# Wacky_Racer_Schematic.net
KiCad netlist of a schematic drawn in Altium Designer
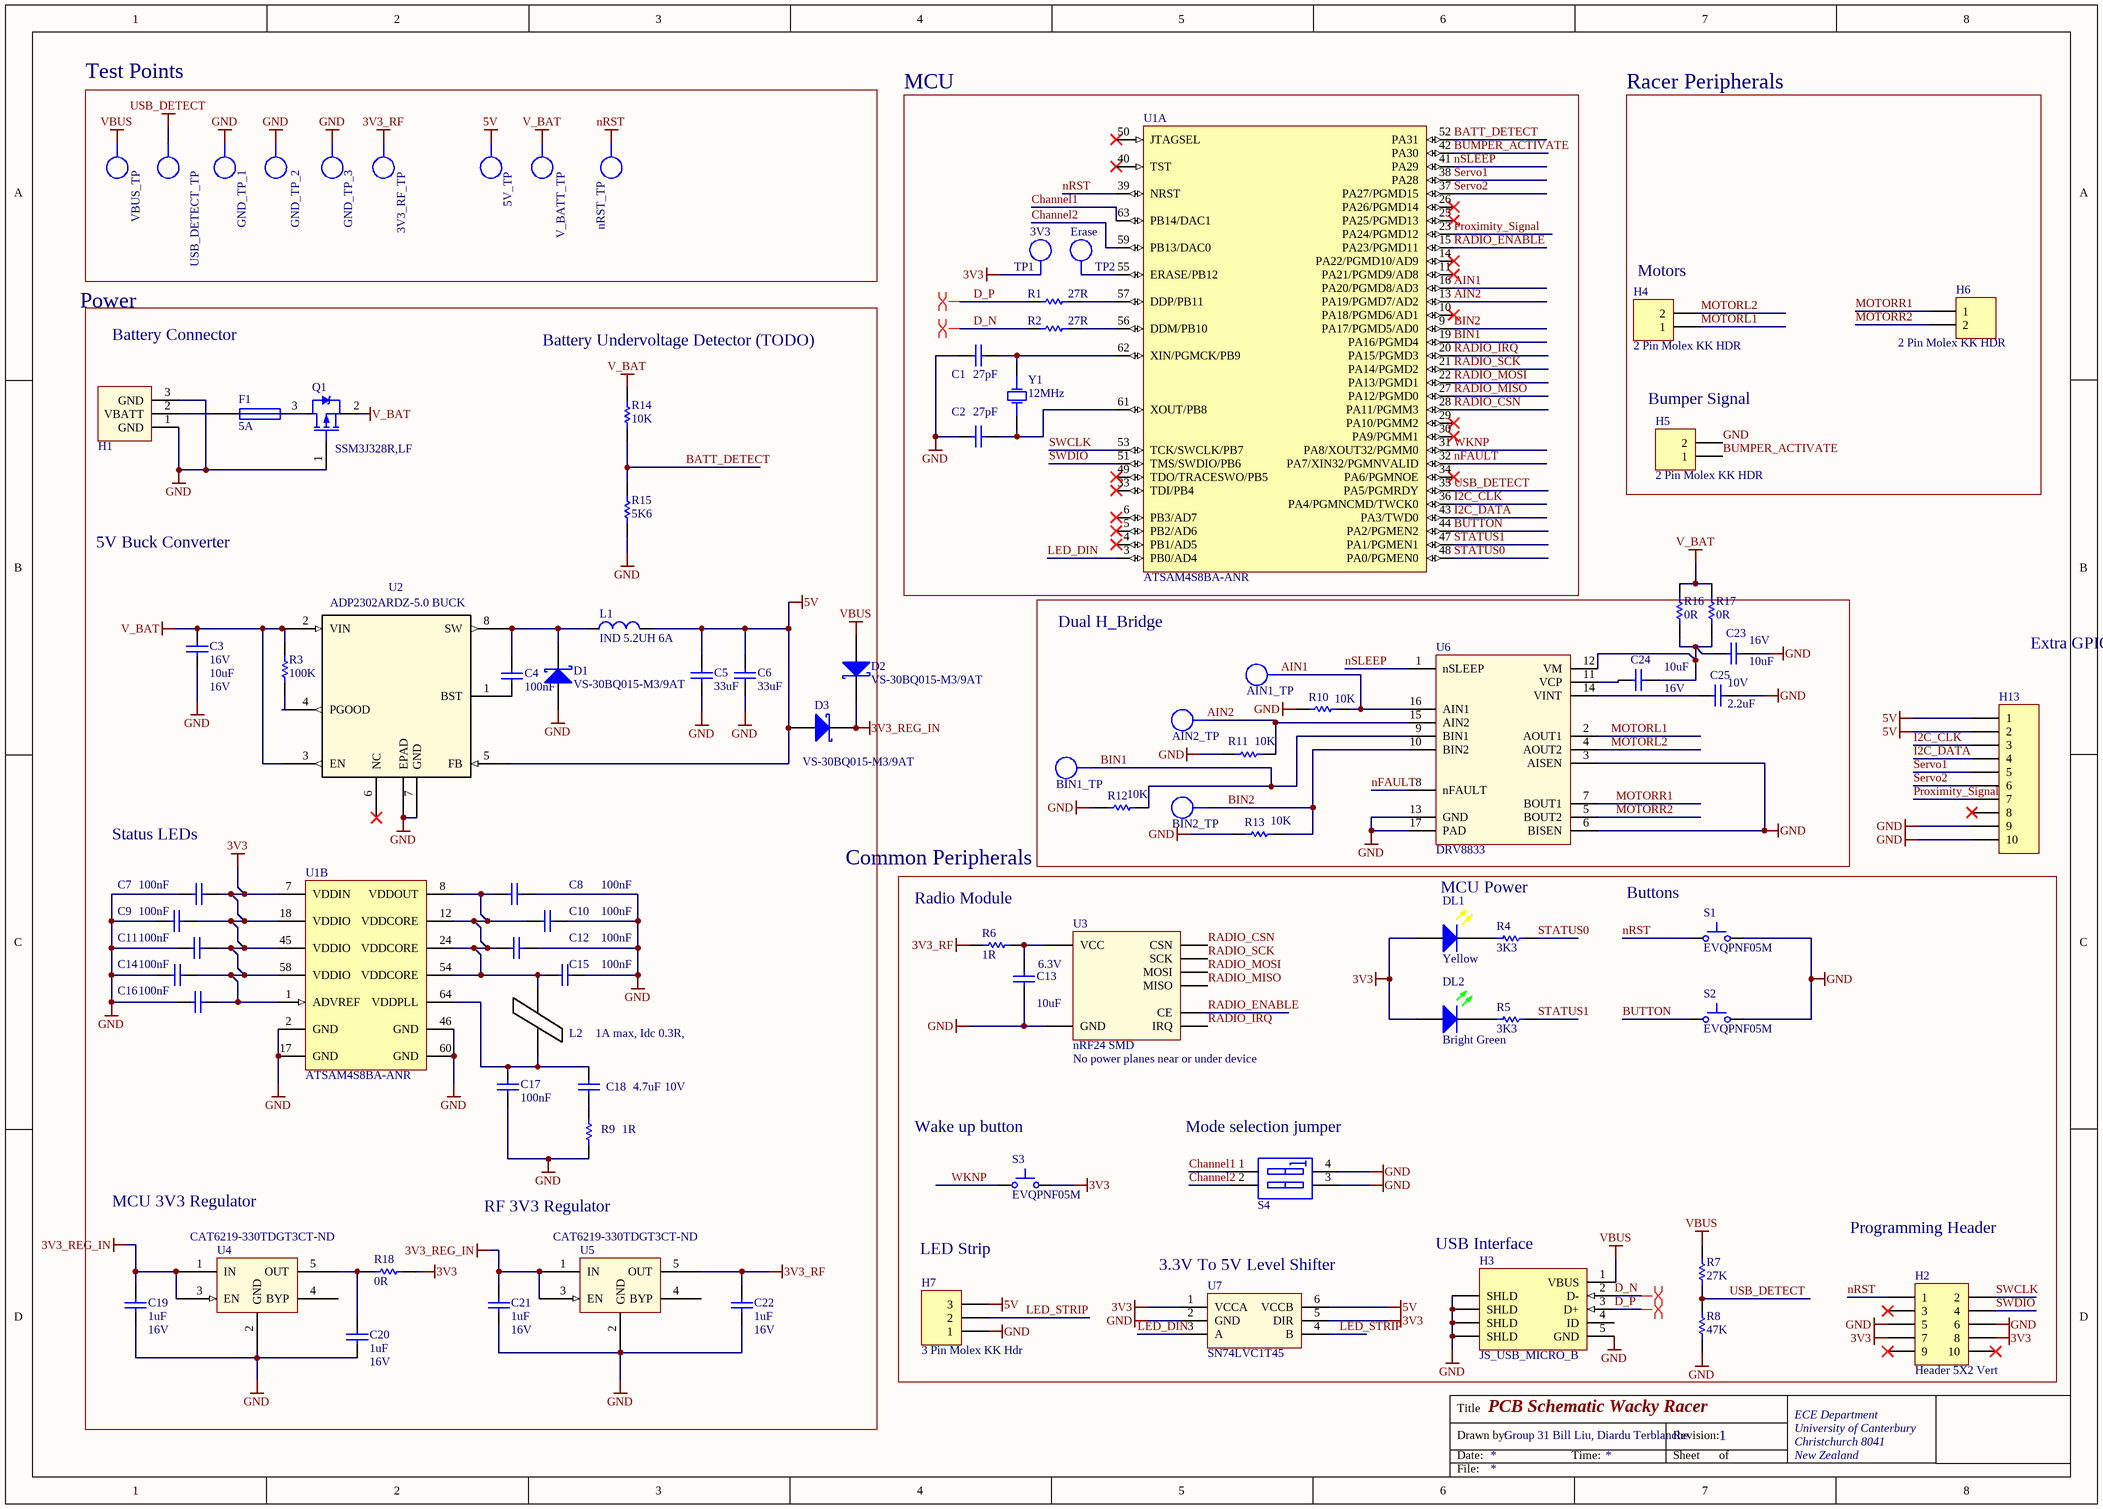
[diagram p0: Wacky Racer Schematic.schdoc]

(export (version "E")
  (design (tool "Eeschema 10.0.6"))
  (components
    (comp (ref "3V3_RF_TP")
      (value "TP")
      (footprint "TP_1206")
      (description "Test-Point 3.3x1.6x2.1mm SMD")
      (fields
        (field (name "MANUFACTURER") "Harwin Inc")
        (field (name "MANUFACTURER PART NUMBER") "S1751-46R")
      )
      (libsource (lib "ECE AD19Components_19V1") (part "TP_1206"))
    )
    (comp (ref "5V_TP")
      (value "TP")
      (footprint "TP_1206")
      (description "Test-Point 3.3x1.6x2.1mm SMD")
      (fields
        (field (name "MANUFACTURER") "Harwin Inc")
        (field (name "MANUFACTURER PART NUMBER") "S1751-46R")
      )
      (libsource (lib "ECE AD19Components_19V1") (part "TP_1206"))
    )
    (comp (ref "AIN1_TP")
      (value "TP")
      (footprint "TP_1206")
      (description "Test-Point 3.3x1.6x2.1mm SMD")
      (fields
        (field (name "MANUFACTURER") "Harwin Inc")
        (field (name "MANUFACTURER PART NUMBER") "S1751-46R")
      )
      (libsource (lib "ECE AD19Components_19V1") (part "TP_1206"))
    )
    (comp (ref "AIN2_TP")
      (value "TP")
      (footprint "TP_1206")
      (description "Test-Point 3.3x1.6x2.1mm SMD")
      (fields
        (field (name "MANUFACTURER") "Harwin Inc")
        (field (name "MANUFACTURER PART NUMBER") "S1751-46R")
      )
      (libsource (lib "ECE AD19Components_19V1") (part "TP_1206"))
    )
    (comp (ref "BIN1_TP")
      (value "TP")
      (footprint "TP_1206")
      (description "Test-Point 3.3x1.6x2.1mm SMD")
      (fields
        (field (name "MANUFACTURER") "Harwin Inc")
        (field (name "MANUFACTURER PART NUMBER") "S1751-46R")
      )
      (libsource (lib "ECE AD19Components_19V1") (part "TP_1206"))
    )
    (comp (ref "BIN2_TP")
      (value "TP")
      (footprint "TP_1206")
      (description "Test-Point 3.3x1.6x2.1mm SMD")
      (fields
        (field (name "MANUFACTURER") "Harwin Inc")
        (field (name "MANUFACTURER PART NUMBER") "S1751-46R")
      )
      (libsource (lib "ECE AD19Components_19V1") (part "TP_1206"))
    )
    (comp (ref "C1")
      (value "27pF")
      (footprint "CAPC1608L")
      (description "CAP CER 27pF NPO/COG +-5% 50V 0603")
      (libsource (lib "ECE AD19Components_19V1") (part "CC_27pF_0603"))
    )
    (comp (ref "C2")
      (value "27pF")
      (footprint "CAPC1608L")
      (description "CAP CER 27pF NPO/COG +-5% 50V 0603")
      (libsource (lib "ECE AD19Components_19V1") (part "CC_27pF_0603"))
    )
    (comp (ref "C3")
      (value "10uF")
      (footprint "CAPC2012L")
      (description "CAP CER 10uF X5R 16V 0805")
      (fields
        (field (name "MANUFACTURER") "Samsung Electro-Mechanics")
        (field (name "MANUFACTURER PART NUMBER") "CL21A106KOQNNWE")
        (field (name "VOLTAGE - RATED") "16V")
        (field (name "MAX VOLTAGE") "16V")
      )
      (libsource (lib "ENCE461AD19_19V2") (part "CC_10uF_16V_0805"))
    )
    (comp (ref "C4")
      (value "100nF")
      (footprint "CAPC1608L")
      (description "CAP CER 100nF X7R +-10% 50V 0603")
      (libsource (lib "ECE AD19Components_19V1") (part "CC_100nF_0603"))
    )
    (comp (ref "C5")
      (value "33uF")
      (footprint "CAPC2012L")
      (description "CAP CER 33uF X5R 6V3 0805")
      (fields
        (field (name "MANUFACTURER") "TDK Corporation")
        (field (name "MANUFACTURER PART NUMBER") "C2012X5R0J336M125AC")
      )
      (libsource (lib "ENCE461AD19_19V2") (part "CC_33uF_6V3_0805"))
    )
    (comp (ref "C6")
      (value "33uF")
      (footprint "CAPC2012L")
      (description "CAP CER 33uF X5R 6V3 0805")
      (fields
        (field (name "MANUFACTURER") "TDK Corporation")
        (field (name "MANUFACTURER PART NUMBER") "C2012X5R0J336M125AC")
      )
      (libsource (lib "ENCE461AD19_19V2") (part "CC_33uF_6V3_0805"))
    )
    (comp (ref "C7")
      (value "100nF")
      (footprint "CAPC1608L")
      (description "CAP CER 100nF X7R +-10% 50V 0603")
      (libsource (lib "ECE AD19Components_19V1") (part "CC_100nF_0603"))
    )
    (comp (ref "C8")
      (value "100nF")
      (footprint "CAPC1608L")
      (description "CAP CER 100nF X7R +-10% 50V 0603")
      (libsource (lib "ECE AD19Components_19V1") (part "CC_100nF_0603"))
    )
    (comp (ref "C9")
      (value "100nF")
      (footprint "CAPC1608L")
      (description "CAP CER 100nF X7R +-10% 50V 0603")
      (libsource (lib "ECE AD19Components_19V1") (part "CC_100nF_0603"))
    )
    (comp (ref "C10")
      (value "100nF")
      (footprint "CAPC1608L")
      (description "CAP CER 100nF X7R +-10% 50V 0603")
      (libsource (lib "ECE AD19Components_19V1") (part "CC_100nF_0603"))
    )
    (comp (ref "C11")
      (value "100nF")
      (footprint "CAPC1608L")
      (description "CAP CER 100nF X7R +-10% 50V 0603")
      (libsource (lib "ECE AD19Components_19V1") (part "CC_100nF_0603"))
    )
    (comp (ref "C12")
      (value "100nF")
      (footprint "CAPC1608L")
      (description "CAP CER 100nF X7R +-10% 50V 0603")
      (libsource (lib "ECE AD19Components_19V1") (part "CC_100nF_0603"))
    )
    (comp (ref "C13")
      (value "10uF")
      (footprint "CAPC1608L")
      (description "CAP CER 10UF X5R +-20% 6V3 0603")
      (fields (field (name "VOLTAGE - RATED") "6.3V"))
      (libsource (lib "ECE AD19Components_19V1") (part "CC_10uF_0603"))
    )
    (comp (ref "C14")
      (value "100nF")
      (footprint "CAPC1608L")
      (description "CAP CER 100nF X7R +-10% 50V 0603")
      (libsource (lib "ECE AD19Components_19V1") (part "CC_100nF_0603"))
    )
    (comp (ref "C15")
      (value "100nF")
      (footprint "CAPC1608L")
      (description "CAP CER 100nF X7R +-10% 50V 0603")
      (libsource (lib "ECE AD19Components_19V1") (part "CC_100nF_0603"))
    )
    (comp (ref "C16")
      (value "100nF")
      (footprint "CAPC1608L")
      (description "CAP CER 100nF X7R +-10% 50V 0603")
      (libsource (lib "ECE AD19Components_19V1") (part "CC_100nF_0603"))
    )
    (comp (ref "C17")
      (value "100nF")
      (footprint "CAPC1608L")
      (description "CAP CER 100nF X7R +-10% 50V 0603")
      (libsource (lib "ECE AD19Components_19V1") (part "CC_100nF_0603"))
    )
    (comp (ref "C18")
      (value "4.7uF")
      (footprint "CAPC1608N")
      (description "CAP CER 4.7uF X5R +-20%  10V 0603")
      (fields (field (name "MAX VOLTAGE") "10V"))
      (libsource (lib "ECE AD19Components_19V1") (part "CC_4.7uF_0603"))
    )
    (comp (ref "C19")
      (value "1uF")
      (footprint "CAPC1608L")
      (description "CAP CER 1uF Y5V -20% +80% 16V 0603")
      (fields (field (name "MAX VOLTAGE") "16V"))
      (libsource (lib "ECE AD19Components_19V1") (part "CC_1uF_0603"))
    )
    (comp (ref "C20")
      (value "1uF")
      (footprint "CAPC1608L")
      (description "CAP CER 1uF Y5V -20% +80% 16V 0603")
      (fields (field (name "MAX VOLTAGE") "16V"))
      (libsource (lib "ECE AD19Components_19V1") (part "CC_1uF_0603"))
    )
    (comp (ref "C21")
      (value "1uF")
      (footprint "CAPC1608L")
      (description "CAP CER 1uF Y5V -20% +80% 16V 0603")
      (fields (field (name "MAX VOLTAGE") "16V"))
      (libsource (lib "ECE AD19Components_19V1") (part "CC_1uF_0603"))
    )
    (comp (ref "C22")
      (value "1uF")
      (footprint "CAPC1608L")
      (description "CAP CER 1uF Y5V -20% +80% 16V 0603")
      (fields (field (name "MAX VOLTAGE") "16V"))
      (libsource (lib "ECE AD19Components_19V1") (part "CC_1uF_0603"))
    )
    (comp (ref "C23")
      (value "10uF")
      (footprint "CAPC2012L")
      (description "CAP CER 10uF X5R 16V 0805")
      (fields
        (field (name "MANUFACTURER") "Samsung Electro-Mechanics")
        (field (name "MANUFACTURER PART NUMBER") "CL21A106KOQNNWE")
        (field (name "VOLTAGE - RATED") "16V")
      )
      (libsource (lib "ENCE461AD19_19V2") (part "CC_10uF_16V_0805"))
    )
    (comp (ref "C24")
      (value "10uF")
      (footprint "CAPC2012L")
      (description "CAP CER 10uF X5R 16V 0805")
      (fields
        (field (name "MANUFACTURER") "Samsung Electro-Mechanics")
        (field (name "MANUFACTURER PART NUMBER") "CL21A106KOQNNWE")
        (field (name "VOLTAGE - RATED") "16V")
      )
      (libsource (lib "ENCE461AD19_19V2") (part "CC_10uF_16V_0805"))
    )
    (comp (ref "C25")
      (value "2.2uF")
      (footprint "CAPC1608L")
      (description "CAP CER 2.2uF X5R +-20% 10V 0603")
      (fields (field (name "MAX VOLTAGE") "10V"))
      (libsource (lib "ECE AD19Components_19V1") (part "CC_2.2uF_0603"))
    )
    (comp (ref "D1")
      (value "VS-30BQ015-M3/9AT")
      (footprint "SMC")
      (description "DIODE, SCHOTTKY, 3A, 15V, DO-214AB / SMC")
      (fields (field (name "MANUFACTURER") "Vishay Semiconductors"))
      (libsource (lib "ECE AD19Components_19V1") (part "DS_VS-30BQ015-M3"))
    )
    (comp (ref "D2")
      (value "VS-30BQ015-M3/9AT")
      (footprint "SMC")
      (description "DIODE, SCHOTTKY, 3A, 15V, DO-214AB / SMC")
      (fields (field (name "MANUFACTURER") "Vishay Semiconductors"))
      (libsource (lib "ECE AD19Components_19V1") (part "DS_VS-30BQ015-M3"))
    )
    (comp (ref "D3")
      (value "VS-30BQ015-M3/9AT")
      (footprint "SMC")
      (description "DIODE, SCHOTTKY, 3A, 15V, DO-214AB / SMC")
      (fields (field (name "MANUFACTURER") "Vishay Semiconductors"))
      (libsource (lib "ECE AD19Components_19V1") (part "DS_VS-30BQ015-M3"))
    )
    (comp (ref "DL1")
      (value "Yellow")
      (footprint "WL-SMCW0603")
      (description "LED Yellow 120mcd 0603 SMD")
      (fields
        (field (name "MANUFACTURER") "WURTH ELEKTRONIK")
        (field (name "MANUFACTURER PART NUMBER") "150060YS75000")
        (field (name "LED COLOUR") "Yellow")
      )
      (libsource (lib "ECE AD19Components_19V1") (part "DL_150060YS75000"))
    )
    (comp (ref "DL2")
      (value "Bright Green")
      (footprint "WL-SMCW0603")
      (description "LED Bright Green 40mcd 0603 SMD")
      (fields
        (field (name "MANUFACTURER") "WURTH ELEKTRONIK")
        (field (name "MANUFACTURER PART NUMBER") "150060VS75000")
        (field (name "LED COLOUR") "Bright Green")
      )
      (libsource (lib "ECE AD19Components_19V1") (part "DL_150060VS75000"))
    )
    (comp (ref "F1")
      (value "5A")
      (footprint "RESC3216N")
      (description "Fuse 5.0A Fast Acting 1206 SMD")
      (fields (field (name "MANUFACTURER PART NUMBER") "C1F5") (field (name "MANUFACTURER") "Bel TRP"))
      (libsource (lib "ECE AD19Components_19V1") (part "FS_Fuse_5.0A"))
    )
    (comp (ref "GND_TP_1")
      (value "TP")
      (footprint "TP_1206")
      (description "Test-Point 3.3x1.6x2.1mm SMD")
      (fields
        (field (name "MANUFACTURER") "Harwin Inc")
        (field (name "MANUFACTURER PART NUMBER") "S1751-46R")
      )
      (libsource (lib "ECE AD19Components_19V1") (part "TP_1206"))
    )
    (comp (ref "GND_TP_2")
      (value "TP")
      (footprint "TP_1206")
      (description "Test-Point 3.3x1.6x2.1mm SMD")
      (fields
        (field (name "MANUFACTURER") "Harwin Inc")
        (field (name "MANUFACTURER PART NUMBER") "S1751-46R")
      )
      (libsource (lib "ECE AD19Components_19V1") (part "TP_1206"))
    )
    (comp (ref "GND_TP_3")
      (value "TP")
      (footprint "TP_1206")
      (description "Test-Point 3.3x1.6x2.1mm SMD")
      (fields
        (field (name "MANUFACTURER") "Harwin Inc")
        (field (name "MANUFACTURER PART NUMBER") "S1751-46R")
      )
      (libsource (lib "ECE AD19Components_19V1") (part "TP_1206"))
    )
    (comp (ref "H1")
      (value "Battery_HEADER_3pin")
      (footprint "BATT_HEADER_3POS")
      (description "3Pin Header 2.54mm spacing")
      (libsource (lib "ENCE461AD19_19V2") (part "Battery_HEADER_3pin"))
    )
    (comp (ref "H2")
      (value "Header 5X2 Vert")
      (footprint "IDC2.54-V10D")
      (description "IDC Header, 2,54mm, 10-Pin, Vert")
      (libsource (lib "ECE AD19Components_19V1") (part "JA_HDR_IDC_5X2_VERT"))
    )
    (comp (ref "H3")
      (value "JS_USB_MICRO_B")
      (footprint "FCI_USB_10118194-0001LF")
      (description "CONN USB MICRO B RECPT SMT R/A")
      (fields (field (name "MANUFACTURER") "FCI") (field (name "MANUFACTURER PART NUMBER") "10118194-0001LF"))
      (libsource (lib "ECE AD19Components_19V1") (part "JS_USB_MICRO_B_SMT"))
    )
    (comp (ref "H4")
      (value "2 Pin Molex KK HDR")
      (footprint "MOLEX_KK_2_HDR")
      (description "CONN HEADER 2POS 2.54mm VERT_Thru Hole")
      (libsource (lib "ECE AD19Components_19V1") (part "JA_MOLEX_KK_2POS"))
    )
    (comp (ref "H5")
      (value "2 Pin Molex KK HDR")
      (footprint "MOLEX_KK_2_HDR")
      (description "CONN HEADER 2POS 2.54mm VERT_Thru Hole")
      (libsource (lib "ECE AD19Components_19V1") (part "JA_MOLEX_KK_2POS"))
    )
    (comp (ref "H6")
      (value "2 Pin Molex KK HDR")
      (footprint "MOLEX_KK_2_HDR")
      (description "CONN HEADER 2POS 2.54mm VERT_Thru Hole")
      (libsource (lib "") (part "JA_MOLEX_KK_2POS_1"))
    )
    (comp (ref "H7")
      (value "3 Pin Molex KK Hdr")
      (footprint "MOLEX_KK_3_HDR")
      (description "CONN HEADER 3POS 2.54mm VERT_Thru Hole")
      (fields (field (name "MANUFACTURER") "Molex"))
      (libsource (lib "ECE AD19Components_19V1") (part "JA_MOLEX_KK_3POS"))
    )
    (comp (ref "H13")
      (value "~")
      (footprint "MOLEX_KK_10_HDR")
      (description "CONN HEADER 10POS 2.54mm VERT_ Thru Hole")
      (libsource (lib "ECE AD19Components_19V1") (part "JA_MOLEX_KK_10POS"))
    )
    (comp (ref "L1")
      (value "IND 5.2UH 6A")
      (footprint "INDUCTOR5u2")
      (description "FIXED IND 5.2UH 6A 22 MOHM SMD")
      (fields
        (field (name "MANUFACTURER") "Sumida America Components Inc.")
        (field (name "MANUFACTURER PART NUMBER") "CDRH104RNP-5R2NC")
      )
      (libsource (lib "ENCE461AD19_19V2") (part "CDRH104RNP-5R2NC"))
    )
    (comp (ref "L2")
      (value "1A max, Idc 0.3R,")
      (footprint "INDC3216L")
      (description "Ferrite Bead, Rdc 0.3R, Z100MHZ 600R, Imax 1A, SMD 1206")
      (fields
        (field (name "MANUFACTURER") "FAIR-RITE")
        (field (name "MANUFACTURER PART NUMBER") "2512066017Y1")
      )
      (libsource (lib "ECE AD19Components_19V1") (part "IN_Ferrite-Bead"))
    )
    (comp (ref "nRST_TP")
      (value "TP")
      (footprint "TP_1206")
      (description "Test-Point 3.3x1.6x2.1mm SMD")
      (fields
        (field (name "MANUFACTURER") "Harwin Inc")
        (field (name "MANUFACTURER PART NUMBER") "S1751-46R")
      )
      (libsource (lib "ECE AD19Components_19V1") (part "TP_1206"))
    )
    (comp (ref "Q1")
      (value "SSM3J328R,LF")
      (footprint "SOT23_L")
      (description "MOSFET P-CH 20V 6A SOT23-3")
      (fields
        (field (name "MANUFACTURER") "Toshiba")
        (field (name "MANUFACTURER PART NUMBER") "SSM3J328R,LF")
      )
      (libsource (lib "ECE AD19Components_19V1") (part "TM_SSM3J328R"))
    )
    (comp (ref "R1")
      (value "27R")
      (footprint "RESC1608L")
      (description "RES 27 OHM 1/10W 5% 0603 SMD")
      (libsource (lib "ECE AD19Components_19V1") (part "RS_27R"))
    )
    (comp (ref "R2")
      (value "27R")
      (footprint "RESC1608L")
      (description "RES 27 OHM 1/10W 5% 0603 SMD")
      (libsource (lib "ECE AD19Components_19V1") (part "RS_27R"))
    )
    (comp (ref "R3")
      (value "100K")
      (footprint "RESC1608L")
      (description "RES 100K OHM 1/10W 5% 0603 SMD")
      (libsource (lib "ECE AD19Components_19V1") (part "RS_100K"))
    )
    (comp (ref "R4")
      (value "3K3")
      (footprint "RESC1608L")
      (description "RES 3.3K OHM 1/10W 5% 0603 SMD")
      (libsource (lib "ECE AD19Components_19V1") (part "RS_3K3"))
    )
    (comp (ref "R5")
      (value "3K3")
      (footprint "RESC1608L")
      (description "RES 3.3K OHM 1/10W 5% 0603 SMD")
      (libsource (lib "ECE AD19Components_19V1") (part "RS_3K3"))
    )
    (comp (ref "R6")
      (value "1R")
      (footprint "RESC3216L")
      (description "RES 1R OHM 1/4W 5% 1206 SMD")
      (libsource (lib "ECE AD19Components_19V1") (part "RT_1R"))
    )
    (comp (ref "R7")
      (value "27K")
      (footprint "RESC1608L")
      (description "RES 27K OHM 1/10W 5% 0603 SMD")
      (libsource (lib "ECE AD19Components_19V1") (part "RS_27K"))
    )
    (comp (ref "R8")
      (value "47K")
      (footprint "RESC1608N")
      (description "RES 47.0K OHM 1/10W 5% 0603 SMD")
      (libsource (lib "ECE AD19Components_19V1") (part "RS_47K"))
    )
    (comp (ref "R9")
      (value "1R")
      (footprint "RESC3216L")
      (description "RES 1R OHM 1/4W 5% 1206 SMD")
      (libsource (lib "ECE AD19Components_19V1") (part "RT_1R"))
    )
    (comp (ref "R10")
      (value "10K")
      (footprint "RESC1608L")
      (description "RES 10.0K OHM 1/10W 5% 0603 SMD")
      (libsource (lib "ECE AD19Components_19V1") (part "RS_10K"))
    )
    (comp (ref "R11")
      (value "10K")
      (footprint "RESC1608L")
      (description "RES 10.0K OHM 1/10W 5% 0603 SMD")
      (libsource (lib "ECE AD19Components_19V1") (part "RS_10K"))
    )
    (comp (ref "R12")
      (value "10K")
      (footprint "RESC1608L")
      (description "RES 10.0K OHM 1/10W 5% 0603 SMD")
      (libsource (lib "ECE AD19Components_19V1") (part "RS_10K"))
    )
    (comp (ref "R13")
      (value "10K")
      (footprint "RESC1608L")
      (description "RES 10.0K OHM 1/10W 5% 0603 SMD")
      (libsource (lib "ECE AD19Components_19V1") (part "RS_10K"))
    )
    (comp (ref "R14")
      (value "10K")
      (footprint "RESC1608L")
      (description "RES 10.0K OHM 1/10W 5% 0603 SMD")
      (libsource (lib "ECE AD19Components_19V1") (part "RS_10K"))
    )
    (comp (ref "R15")
      (value "5K6")
      (footprint "RESC1608L")
      (description "RES 5.6K OHM 1/10W 5% 0603 SMD")
      (libsource (lib "ECE AD19Components_19V1") (part "RS_5K6"))
    )
    (comp (ref "R16")
      (value "0R")
      (footprint "RESC1608L")
      (description "RES 0.0 OHM 1/10W 5% 0603 SMD")
      (libsource (lib "ECE AD19Components_19V1") (part "RS_0R0"))
    )
    (comp (ref "R17")
      (value "0R")
      (footprint "RESC1608L")
      (description "RES 0.0 OHM 1/10W 5% 0603 SMD")
      (libsource (lib "ECE AD19Components_19V1") (part "RS_0R0"))
    )
    (comp (ref "R18")
      (value "0R")
      (footprint "RESC1608L")
      (description "RES 0.0 OHM 1/10W 5% 0603 SMD")
      (libsource (lib "ECE AD19Components_19V1") (part "RS_0R0"))
    )
    (comp (ref "S1")
      (value "EVQPNF05M")
      (footprint "EVQPNF05M")
      (description "Panasonic 6 x 3.5mm SMD Light Touch Switch Type SMD")
      (fields (field (name "MANUFACTURER") "Panasonic"))
      (libsource (lib "ECE AD19Components_19V1") (part "WS_EVQPNF05M"))
    )
    (comp (ref "S2")
      (value "EVQPNF05M")
      (footprint "EVQPNF05M")
      (description "Panasonic 6 x 3.5mm SMD Light Touch Switch Type SMD")
      (fields (field (name "MANUFACTURER") "Panasonic"))
      (libsource (lib "ECE AD19Components_19V1") (part "WS_EVQPNF05M"))
    )
    (comp (ref "S3")
      (value "EVQPNF05M")
      (footprint "EVQPNF05M")
      (description "Panasonic 6 x 3.5mm SMD Light Touch Switch Type SMD")
      (fields (field (name "MANUFACTURER") "Panasonic"))
      (libsource (lib "ECE AD19Components_19V1") (part "WS_EVQPNF05M"))
    )
    (comp (ref "S4")
      (value "WS_SW DIP-2")
      (footprint "DIP_SW_2WAY_SMD")
      (description "DIP Switch, 2 Position, SPST SMD")
      (fields
        (field (name "MANUFACTURER") "OMRON ELECTRONIC COMPONENTS")
        (field (name "MANUFACTURER PART NUMBER") "A6SN-2101")
      )
      (libsource (lib "ECE AD19Components_19V1") (part "WS_SW DIP-2"))
    )
    (comp (ref "TP1")
      (value "3V3")
      (footprint "TP_1206")
      (description "Test-Point 3.3x1.6x2.1mm SMD")
      (fields
        (field (name "MANUFACTURER") "Harwin Inc")
        (field (name "MANUFACTURER PART NUMBER") "S1751-46R")
      )
      (libsource (lib "ECE AD19Components_19V1") (part "TP_1206"))
    )
    (comp (ref "TP2")
      (value "Erase")
      (footprint "TP_1206")
      (description "Test-Point 3.3x1.6x2.1mm SMD")
      (fields
        (field (name "MANUFACTURER") "Harwin Inc")
        (field (name "MANUFACTURER PART NUMBER") "S1751-46R")
      )
      (libsource (lib "ECE AD19Components_19V1") (part "TP_1206"))
    )
    (comp (ref "U1")
      (value "ATSAM4S8BA-ANR")
      (footprint "LQFP64_L")
      (description "IC MCU 32BIT 512KB FLASH 64LQFP")
      (fields (field (name "MANUFACTURER") "Atmel"))
      (libsource (lib "ECE AD19Components_19V1") (part "SE_ATSAM4S16BA-MU"))
    )
    (comp (ref "U2")
      (value "ADP2302ARDZ-5.0 BUCK")
      (footprint "RD_8_1")
      (description "IC REG BUCK 5V 2A 8SOIC")
      (fields (field (name "MANUFACTURER_PART_NUMBER") "ADP2302ARDZ-5.0-R7"))
      (libsource (lib "ENCE461AD19_19V2") (part "ADP2302ARDZ-5.0-R7"))
    )
    (comp (ref "U3")
      (value "nRF24 SMD")
      (footprint "NRF24")
      (description "nRF24 SMD Module")
      (fields (field (name "WARNING") "No power planes near or under device"))
      (libsource (lib "ENCE461AD19_19V2") (part "NRF24"))
    )
    (comp (ref "U4")
      (value "CAT6219-330TDGT3")
      (footprint "SOT95P280X145-5N")
      (description "IC REG LIN 3.3V 500MA TSOT23-5")
      (fields
        (field (name "BASE PART NUMBER") "CAT6219")
        (field (name "SUPPLIER PART NUMBER") "CAT6219-330TDGT3CT-ND")
      )
      (libsource (lib "ENCE461AD19_19V2") (part "SV_CAT6219-330TDGT3"))
    )
    (comp (ref "U5")
      (value "CAT6219-330TDGT3")
      (footprint "SOT95P280X145-5N")
      (description "IC REG LIN 3.3V 500MA TSOT23-5")
      (fields
        (field (name "BASE PART NUMBER") "CAT6219")
        (field (name "SUPPLIER PART NUMBER") "CAT6219-330TDGT3CT-ND")
      )
      (libsource (lib "ENCE461AD19_19V2") (part "SV_CAT6219-330TDGT3"))
    )
    (comp (ref "U6")
      (value "DRV8833")
      (footprint "HTSOP16")
      (description "Dual H-Bridge Motor Driver 1.5A")
      (libsource (lib "ENCE461AD19_19V2") (part "DRV8833"))
    )
    (comp (ref "U7")
      (value "SN74LVC1T45")
      (footprint "SOT23-6_N")
      (description "1.8V - 5V level converter")
      (libsource (lib "ENCE461_extras_2020") (part "SN74LVC1T45"))
    )
    (comp (ref "USB_DETECT_TP")
      (value "TP")
      (footprint "TP_1206")
      (description "Test-Point 3.3x1.6x2.1mm SMD")
      (fields
        (field (name "MANUFACTURER") "Harwin Inc")
        (field (name "MANUFACTURER PART NUMBER") "S1751-46R")
      )
      (libsource (lib "ECE AD19Components_19V1") (part "TP_1206"))
    )
    (comp (ref "VBUS_TP")
      (value "TP")
      (footprint "TP_1206")
      (description "Test-Point 3.3x1.6x2.1mm SMD")
      (fields
        (field (name "MANUFACTURER") "Harwin Inc")
        (field (name "MANUFACTURER PART NUMBER") "S1751-46R")
      )
      (libsource (lib "ECE AD19Components_19V1") (part "TP_1206"))
    )
    (comp (ref "V_BATT_TP")
      (value "TP")
      (footprint "TP_1206")
      (description "Test-Point 3.3x1.6x2.1mm SMD")
      (fields
        (field (name "MANUFACTURER") "Harwin Inc")
        (field (name "MANUFACTURER PART NUMBER") "S1751-46R")
      )
      (libsource (lib "ECE AD19Components_19V1") (part "TP_1206"))
    )
    (comp (ref "Y1")
      (value "12MHz")
      (footprint "6.0X3.5-4")
      (description "CRYSTAL 12MHZ 18PF 6X3.5mm SMD")
      (fields
        (field (name "MANUFACTURER") "CTS-Frequency Controls")
        (field (name "MANUFACTURER PART NUMBER") "406C35D12M00000")
        (field (name "FREQUENCY") "12MHz")
      )
      (libsource (lib "ECE AD19Components_19V1") (part "XT_CRYSTAL_12MHz_18pF"))
    )
  )
  (nets
    (net (code "2") (name "/AIN1") (class "Default")
      (node (ref "AIN1_TP") (pin "1") (pinfunction "1_1") (pintype "passive"))
      (node (ref "R10") (pin "2") (pinfunction "2_2") (pintype "passive"))
      (node (ref "U1") (pin "16") (pinfunction "PA20/PGMD8/AD3_16") (pintype "bidirectional"))
      (node (ref "U6") (pin "16") (pinfunction "AIN1_16") (pintype "passive"))
    )
    (net (code "3") (name "/AIN2") (class "Default")
      (node (ref "AIN2_TP") (pin "1") (pinfunction "1_1") (pintype "passive"))
      (node (ref "R11") (pin "2") (pinfunction "2_2") (pintype "passive"))
      (node (ref "U1") (pin "13") (pinfunction "PA19/PGMD7/AD2_13") (pintype "bidirectional"))
      (node (ref "U6") (pin "15") (pinfunction "AIN2_15") (pintype "passive"))
    )
    (net (code "4") (name "/BATT_DETECT") (class "Default")
      (node (ref "R14") (pin "1") (pinfunction "1_1") (pintype "passive"))
      (node (ref "R15") (pin "2") (pinfunction "2_2") (pintype "passive"))
      (node (ref "U1") (pin "52") (pinfunction "PA31_52") (pintype "bidirectional"))
    )
    (net (code "5") (name "/BIN1") (class "Default")
      (node (ref "BIN1_TP") (pin "1") (pinfunction "1_1") (pintype "passive"))
      (node (ref "R12") (pin "2") (pinfunction "2_2") (pintype "passive"))
      (node (ref "U1") (pin "19") (pinfunction "PA16/PGMD4_19") (pintype "bidirectional"))
      (node (ref "U6") (pin "9") (pinfunction "BIN1_9") (pintype "passive"))
    )
    (net (code "6") (name "/BIN2") (class "Default")
      (node (ref "BIN2_TP") (pin "1") (pinfunction "1_1") (pintype "passive"))
      (node (ref "R13") (pin "2") (pinfunction "2_2") (pintype "passive"))
      (node (ref "U1") (pin "9") (pinfunction "PA17/PGMD5/AD0_9") (pintype "bidirectional"))
      (node (ref "U6") (pin "10") (pinfunction "BIN2_10") (pintype "passive"))
    )
    (net (code "7") (name "/BUMPER_ACTIVATE") (class "Default")
      (node (ref "H5") (pin "1") (pinfunction "1_1") (pintype "passive"))
      (node (ref "U1") (pin "42") (pinfunction "PA30_42") (pintype "bidirectional"))
    )
    (net (code "8") (name "/BUTTON") (class "Default")
      (node (ref "S2") (pin "1") (pintype "passive"))
      (node (ref "U1") (pin "44") (pinfunction "PA2/PGMEN2_44") (pintype "bidirectional"))
    )
    (net (code "9") (name "/Channel1") (class "Default")
      (node (ref "S4") (pin "1") (pinfunction "A1_1") (pintype "passive"))
      (node (ref "U1") (pin "63") (pinfunction "PB14/DAC1_63") (pintype "bidirectional"))
    )
    (net (code "10") (name "/Channel2") (class "Default")
      (node (ref "S4") (pin "2") (pinfunction "A2_2") (pintype "passive"))
      (node (ref "U1") (pin "59") (pinfunction "PB13/DAC0_59") (pintype "bidirectional"))
    )
    (net (code "11") (name "/D_N") (class "Default")
      (node (ref "H3") (pin "2") (pinfunction "D-_2") (pintype "input"))
      (node (ref "R2") (pin "1") (pinfunction "1_1") (pintype "passive"))
    )
    (net (code "12") (name "/D_P") (class "Default")
      (node (ref "H3") (pin "3") (pinfunction "D+_3") (pintype "input"))
      (node (ref "R1") (pin "1") (pinfunction "1_1") (pintype "passive"))
    )
    (net (code "13") (name "/I2C_CLK") (class "Default")
      (node (ref "H13") (pin "3") (pinfunction "3_3") (pintype "passive"))
      (node (ref "U1") (pin "36") (pinfunction "PA4/PGMNCMD/TWCK0_36") (pintype "bidirectional"))
    )
    (net (code "14") (name "/I2C_DATA") (class "Default")
      (node (ref "H13") (pin "4") (pinfunction "4_4") (pintype "passive"))
      (node (ref "U1") (pin "43") (pinfunction "PA3/TWD0_43") (pintype "bidirectional"))
    )
    (net (code "15") (name "/LED_DIN") (class "Default")
      (node (ref "U1") (pin "3") (pinfunction "PB0/AD4_3") (pintype "bidirectional"))
      (node (ref "U7") (pin "3") (pinfunction "A_3") (pintype "passive"))
    )
    (net (code "16") (name "/LED_STRIP") (class "Default")
      (node (ref "H7") (pin "2") (pinfunction "2_2") (pintype "passive"))
      (node (ref "U7") (pin "4") (pinfunction "B_4") (pintype "passive"))
    )
    (net (code "17") (name "/MOTORL1") (class "Default")
      (node (ref "H4") (pin "1") (pinfunction "1_1") (pintype "passive"))
      (node (ref "U6") (pin "2") (pinfunction "AOUT1_2") (pintype "passive"))
    )
    (net (code "18") (name "/MOTORL2") (class "Default")
      (node (ref "H4") (pin "2") (pinfunction "2_2") (pintype "passive"))
      (node (ref "U6") (pin "4") (pinfunction "AOUT2_4") (pintype "passive"))
    )
    (net (code "19") (name "/MOTORR1") (class "Default")
      (node (ref "H6") (pin "1") (pinfunction "1_1") (pintype "passive"))
      (node (ref "U6") (pin "7") (pinfunction "BOUT1_7") (pintype "passive"))
    )
    (net (code "20") (name "/MOTORR2") (class "Default")
      (node (ref "H6") (pin "2") (pinfunction "2_2") (pintype "passive"))
      (node (ref "U6") (pin "5") (pinfunction "BOUT2_5") (pintype "passive"))
    )
    (net (code "21") (name "/Proximity_Signal") (class "Default")
      (node (ref "H13") (pin "7") (pinfunction "7_7") (pintype "passive"))
      (node (ref "U1") (pin "23") (pinfunction "PA24/PGMD12_23") (pintype "bidirectional"))
    )
    (net (code "22") (name "/RADIO_CSN") (class "Default")
      (node (ref "U1") (pin "28") (pinfunction "PA11/PGMM3_28") (pintype "bidirectional"))
      (node (ref "U3") (pin "4") (pinfunction "CSN_4") (pintype "passive"))
    )
    (net (code "23") (name "/RADIO_ENABLE") (class "Default")
      (node (ref "U1") (pin "15") (pinfunction "PA23/PGMD11_15") (pintype "bidirectional"))
      (node (ref "U3") (pin "3") (pinfunction "CE_3") (pintype "passive"))
    )
    (net (code "24") (name "/RADIO_IRQ") (class "Default")
      (node (ref "U1") (pin "20") (pinfunction "PA15/PGMD3_20") (pintype "bidirectional"))
      (node (ref "U3") (pin "8") (pinfunction "IRQ_8") (pintype "passive"))
    )
    (net (code "25") (name "/RADIO_MISO") (class "Default")
      (node (ref "U1") (pin "27") (pinfunction "PA12/PGMD0_27") (pintype "bidirectional"))
      (node (ref "U3") (pin "7") (pinfunction "MISO_7") (pintype "passive"))
    )
    (net (code "26") (name "/RADIO_MOSI") (class "Default")
      (node (ref "U1") (pin "22") (pinfunction "PA13/PGMD1_22") (pintype "bidirectional"))
      (node (ref "U3") (pin "6") (pinfunction "MOSI_6") (pintype "passive"))
    )
    (net (code "27") (name "/RADIO_SCK") (class "Default")
      (node (ref "U1") (pin "21") (pinfunction "PA14/PGMD2_21") (pintype "bidirectional"))
      (node (ref "U3") (pin "5") (pinfunction "SCK_5") (pintype "passive"))
    )
    (net (code "28") (name "/STATUS0") (class "Default")
      (node (ref "R4") (pin "2") (pinfunction "2_2") (pintype "passive"))
      (node (ref "U1") (pin "48") (pinfunction "PA0/PGMEN0_48") (pintype "bidirectional"))
    )
    (net (code "29") (name "/STATUS1") (class "Default")
      (node (ref "R5") (pin "2") (pinfunction "2_2") (pintype "passive"))
      (node (ref "U1") (pin "47") (pinfunction "PA1/PGMEN1_47") (pintype "bidirectional"))
    )
    (net (code "30") (name "/SWCLK") (class "Default")
      (node (ref "H2") (pin "2") (pinfunction "2_2") (pintype "passive"))
      (node (ref "U1") (pin "53") (pinfunction "TCK/SWCLK/PB7_53") (pintype "bidirectional"))
    )
    (net (code "31") (name "/SWDIO") (class "Default")
      (node (ref "H2") (pin "4") (pinfunction "4_4") (pintype "passive"))
      (node (ref "U1") (pin "51") (pinfunction "TMS/SWDIO/PB6_51") (pintype "bidirectional"))
    )
    (net (code "32") (name "/Servo1") (class "Default")
      (node (ref "H13") (pin "5") (pinfunction "5_5") (pintype "passive"))
      (node (ref "U1") (pin "38") (pinfunction "PA28_38") (pintype "bidirectional"))
    )
    (net (code "33") (name "/Servo2") (class "Default")
      (node (ref "H13") (pin "6") (pinfunction "6_6") (pintype "passive"))
      (node (ref "U1") (pin "37") (pinfunction "PA27/PGMD15_37") (pintype "bidirectional"))
    )
    (net (code "34") (name "/WKNP") (class "Default")
      (node (ref "S3") (pin "1") (pintype "passive"))
      (node (ref "U1") (pin "31") (pinfunction "PA8/XOUT32/PGMM0_31") (pintype "bidirectional"))
    )
    (net (code "35") (name "/nFAULT") (class "Default")
      (node (ref "U1") (pin "32") (pinfunction "PA7/XIN32/PGMNVALID_32") (pintype "bidirectional"))
      (node (ref "U6") (pin "8") (pinfunction "nFAULT_8") (pintype "passive"))
    )
    (net (code "36") (name "/nSLEEP") (class "Default")
      (node (ref "U1") (pin "41") (pinfunction "PA29_41") (pintype "bidirectional"))
      (node (ref "U6") (pin "1") (pinfunction "nSLEEP_1") (pintype "passive"))
    )
    (net (code "37") (name "3V3") (class "Default")
      (node (ref "C11") (pin "2") (pinfunction "2_2") (pintype "passive"))
      (node (ref "C14") (pin "2") (pinfunction "2_2") (pintype "passive"))
      (node (ref "C16") (pin "2") (pinfunction "2_2") (pintype "passive"))
      (node (ref "C7") (pin "2") (pinfunction "2_2") (pintype "passive"))
      (node (ref "C9") (pin "2") (pinfunction "2_2") (pintype "passive"))
      (node (ref "DL1") (pin "2") (pinfunction "A_2") (pintype "passive"))
      (node (ref "DL2") (pin "2") (pinfunction "A_2") (pintype "passive"))
      (node (ref "H2") (pin "7") (pinfunction "7_7") (pintype "passive"))
      (node (ref "H2") (pin "8") (pinfunction "8_8") (pintype "passive"))
      (node (ref "R18") (pin "2") (pinfunction "2_2") (pintype "passive"))
      (node (ref "S3") (pin "2") (pintype "passive"))
      (node (ref "TP1") (pin "1") (pinfunction "1_1") (pintype "passive"))
      (node (ref "U1") (pin "1") (pinfunction "ADVREF_1") (pintype "input"))
      (node (ref "U1") (pin "18") (pinfunction "VDDIO_18") (pintype "power_in"))
      (node (ref "U1") (pin "45") (pinfunction "VDDIO_45") (pintype "power_in"))
      (node (ref "U1") (pin "58") (pinfunction "VDDIO_58") (pintype "power_in"))
      (node (ref "U1") (pin "7") (pinfunction "VDDIN_7") (pintype "power_in"))
      (node (ref "U7") (pin "1") (pinfunction "VCCA_1") (pintype "passive"))
      (node (ref "U7") (pin "5") (pinfunction "DIR_5") (pintype "passive"))
    )
    (net (code "38") (name "3V3_REG_IN") (class "Default")
      (node (ref "C19") (pin "2") (pinfunction "2_2") (pintype "passive"))
      (node (ref "C21") (pin "2") (pinfunction "2_2") (pintype "passive"))
      (node (ref "D2") (pin "2") (pinfunction "K_2") (pintype "passive"))
      (node (ref "D3") (pin "2") (pinfunction "K_2") (pintype "passive"))
      (node (ref "U4") (pin "1") (pinfunction "IN_1") (pintype "power_in"))
      (node (ref "U4") (pin "3") (pinfunction "EN_3") (pintype "input"))
      (node (ref "U5") (pin "1") (pinfunction "IN_1") (pintype "power_in"))
      (node (ref "U5") (pin "3") (pinfunction "EN_3") (pintype "input"))
    )
    (net (code "39") (name "3V3_RF") (class "Default")
      (node (ref "3V3_RF_TP") (pin "1") (pinfunction "1_1") (pintype "passive"))
      (node (ref "C22") (pin "2") (pinfunction "2_2") (pintype "passive"))
      (node (ref "R6") (pin "1") (pinfunction "1_1") (pintype "passive"))
      (node (ref "U5") (pin "5") (pinfunction "OUT_5") (pintype "power_in"))
    )
    (net (code "40") (name "5V") (class "Default")
      (node (ref "5V_TP") (pin "1") (pinfunction "1_1") (pintype "passive"))
      (node (ref "C5") (pin "2") (pinfunction "2_2") (pintype "passive"))
      (node (ref "C6") (pin "2") (pinfunction "2_2") (pintype "passive"))
      (node (ref "D3") (pin "1") (pinfunction "A_1") (pintype "passive"))
      (node (ref "H13") (pin "1") (pinfunction "1_1") (pintype "passive"))
      (node (ref "H13") (pin "2") (pinfunction "2_2") (pintype "passive"))
      (node (ref "H7") (pin "3") (pinfunction "3_3") (pintype "passive"))
      (node (ref "L1") (pin "2") (pintype "passive"))
      (node (ref "U2") (pin "5") (pinfunction "FB_5") (pintype "input"))
      (node (ref "U7") (pin "6") (pinfunction "VCCB_6") (pintype "passive"))
    )
    (net (code "41") (name "GND") (class "Default")
      (node (ref "C1") (pin "1") (pinfunction "1_1") (pintype "passive"))
      (node (ref "C10") (pin "2") (pinfunction "2_2") (pintype "passive"))
      (node (ref "C11") (pin "1") (pinfunction "1_1") (pintype "passive"))
      (node (ref "C12") (pin "2") (pinfunction "2_2") (pintype "passive"))
      (node (ref "C13") (pin "1") (pinfunction "1_1") (pintype "passive"))
      (node (ref "C14") (pin "1") (pinfunction "1_1") (pintype "passive"))
      (node (ref "C15") (pin "2") (pinfunction "2_2") (pintype "passive"))
      (node (ref "C16") (pin "1") (pinfunction "1_1") (pintype "passive"))
      (node (ref "C17") (pin "1") (pinfunction "1_1") (pintype "passive"))
      (node (ref "C19") (pin "1") (pinfunction "1_1") (pintype "passive"))
      (node (ref "C2") (pin "1") (pinfunction "1_1") (pintype "passive"))
      (node (ref "C20") (pin "1") (pinfunction "1_1") (pintype "passive"))
      (node (ref "C21") (pin "1") (pinfunction "1_1") (pintype "passive"))
      (node (ref "C22") (pin "1") (pinfunction "1_1") (pintype "passive"))
      (node (ref "C23") (pin "2") (pinfunction "2_2") (pintype "passive"))
      (node (ref "C25") (pin "2") (pinfunction "2_2") (pintype "passive"))
      (node (ref "C3") (pin "1") (pinfunction "1_1") (pintype "passive"))
      (node (ref "C5") (pin "1") (pinfunction "1_1") (pintype "passive"))
      (node (ref "C6") (pin "1") (pinfunction "1_1") (pintype "passive"))
      (node (ref "C7") (pin "1") (pinfunction "1_1") (pintype "passive"))
      (node (ref "C8") (pin "2") (pinfunction "2_2") (pintype "passive"))
      (node (ref "C9") (pin "1") (pinfunction "1_1") (pintype "passive"))
      (node (ref "D1") (pin "1") (pinfunction "A_1") (pintype "passive"))
      (node (ref "GND_TP_1") (pin "1") (pinfunction "1_1") (pintype "passive"))
      (node (ref "GND_TP_2") (pin "1") (pinfunction "1_1") (pintype "passive"))
      (node (ref "GND_TP_3") (pin "1") (pinfunction "1_1") (pintype "passive"))
      (node (ref "H1") (pin "1") (pinfunction "GND_1") (pintype "passive"))
      (node (ref "H1") (pin "3") (pinfunction "GND_3") (pintype "passive"))
      (node (ref "H13") (pin "10") (pinfunction "10_10") (pintype "passive"))
      (node (ref "H13") (pin "9") (pinfunction "9_9") (pintype "passive"))
      (node (ref "H2") (pin "5") (pinfunction "5_5") (pintype "passive"))
      (node (ref "H2") (pin "6") (pinfunction "6_6") (pintype "passive"))
      (node (ref "H3") (pin "5") (pinfunction "GND_5") (pintype "passive"))
      (node (ref "H3") (pin "6") (pinfunction "SHLD_6") (pintype "passive"))
      (node (ref "H5") (pin "2") (pinfunction "2_2") (pintype "passive"))
      (node (ref "H7") (pin "1") (pinfunction "1_1") (pintype "passive"))
      (node (ref "Q1") (pin "1") (pinfunction "1_1") (pintype "passive"))
      (node (ref "R10") (pin "1") (pinfunction "1_1") (pintype "passive"))
      (node (ref "R11") (pin "1") (pinfunction "1_1") (pintype "passive"))
      (node (ref "R12") (pin "1") (pinfunction "1_1") (pintype "passive"))
      (node (ref "R13") (pin "1") (pinfunction "1_1") (pintype "passive"))
      (node (ref "R15") (pin "1") (pinfunction "1_1") (pintype "passive"))
      (node (ref "R8") (pin "1") (pinfunction "1_1") (pintype "passive"))
      (node (ref "R9") (pin "1") (pinfunction "1_1") (pintype "passive"))
      (node (ref "S1") (pin "2") (pintype "passive"))
      (node (ref "S2") (pin "2") (pintype "passive"))
      (node (ref "S4") (pin "3") (pinfunction "B2_3") (pintype "passive"))
      (node (ref "S4") (pin "4") (pinfunction "B1_4") (pintype "passive"))
      (node (ref "U1") (pin "17") (pinfunction "GND_17") (pintype "power_in"))
      (node (ref "U1") (pin "2") (pinfunction "GND_2") (pintype "power_in"))
      (node (ref "U1") (pin "46") (pinfunction "GND_46") (pintype "power_in"))
      (node (ref "U1") (pin "60") (pinfunction "GND_60") (pintype "power_in"))
      (node (ref "U2") (pin "7") (pinfunction "GND_7") (pintype "power_in"))
      (node (ref "U2") (pin "EPAD") (pinfunction "EPAD_EPAD") (pintype "passive"))
      (node (ref "U3") (pin "2") (pinfunction "GND_2") (pintype "passive"))
      (node (ref "U4") (pin "2") (pinfunction "GND_2") (pintype "power_in"))
      (node (ref "U5") (pin "2") (pinfunction "GND_2") (pintype "power_in"))
      (node (ref "U6") (pin "13") (pinfunction "GND_13") (pintype "passive"))
      (node (ref "U6") (pin "17") (pinfunction "PAD_17") (pintype "passive"))
      (node (ref "U6") (pin "3") (pinfunction "AISEN_3") (pintype "passive"))
      (node (ref "U6") (pin "6") (pinfunction "BISEN_6") (pintype "passive"))
      (node (ref "U7") (pin "2") (pinfunction "GND_2") (pintype "passive"))
    )
    (net (code "42") (name "Net-(C18-Pad1)") (class "Default")
      (node (ref "C18") (pin "1") (pinfunction "1_1") (pintype "passive"))
      (node (ref "R9") (pin "2") (pinfunction "2_2") (pintype "passive"))
    )
    (net (code "43") (name "Net-(D1-K)") (class "Default")
      (node (ref "C4") (pin "2") (pinfunction "2_2") (pintype "passive"))
      (node (ref "D1") (pin "2") (pinfunction "K_2") (pintype "passive"))
      (node (ref "L1") (pin "1") (pintype "passive"))
      (node (ref "U2") (pin "8") (pinfunction "SW_8") (pintype "output"))
    )
    (net (code "44") (name "Net-(DL1-K)") (class "Default")
      (node (ref "DL1") (pin "1") (pinfunction "K_1") (pintype "passive"))
      (node (ref "R4") (pin "1") (pinfunction "1_1") (pintype "passive"))
    )
    (net (code "45") (name "Net-(DL2-K)") (class "Default")
      (node (ref "DL2") (pin "1") (pinfunction "K_1") (pintype "passive"))
      (node (ref "R5") (pin "1") (pinfunction "1_1") (pintype "passive"))
    )
    (net (code "46") (name "Net-(F1-Pad2)") (class "Default")
      (node (ref "F1") (pin "2") (pinfunction "2_2") (pintype "passive"))
      (node (ref "Q1") (pin "3") (pinfunction "3_3") (pintype "passive"))
    )
    (net (code "47") (name "Net-(H1-VBATT)") (class "Default")
      (node (ref "F1") (pin "1") (pinfunction "1_1") (pintype "passive"))
      (node (ref "H1") (pin "2") (pinfunction "VBATT_2") (pintype "passive"))
    )
    (net (code "48") (name "Net-(U1A-DDM{slash}PB10)") (class "Default")
      (node (ref "R2") (pin "2") (pinfunction "2_2") (pintype "passive"))
      (node (ref "U1") (pin "56") (pinfunction "DDM/PB10_56") (pintype "bidirectional"))
    )
    (net (code "49") (name "Net-(U1A-DDP{slash}PB11)") (class "Default")
      (node (ref "R1") (pin "2") (pinfunction "2_2") (pintype "passive"))
      (node (ref "U1") (pin "57") (pinfunction "DDP/PB11_57") (pintype "bidirectional"))
    )
    (net (code "50") (name "Net-(U1A-ERASE{slash}PB12)") (class "Default")
      (node (ref "TP2") (pin "1") (pinfunction "1_1") (pintype "passive"))
      (node (ref "U1") (pin "55") (pinfunction "ERASE/PB12_55") (pintype "bidirectional"))
    )
    (net (code "51") (name "Net-(U1A-XIN{slash}PGMCK{slash}PB9)") (class "Default")
      (node (ref "C1") (pin "2") (pinfunction "2_2") (pintype "passive"))
      (node (ref "U1") (pin "62") (pinfunction "XIN/PGMCK/PB9_62") (pintype "bidirectional"))
      (node (ref "Y1") (pin "1") (pinfunction "OSC1_1") (pintype "passive"))
    )
    (net (code "52") (name "Net-(U1A-XOUT{slash}PB8)") (class "Default")
      (node (ref "C2") (pin "2") (pinfunction "2_2") (pintype "passive"))
      (node (ref "U1") (pin "61") (pinfunction "XOUT/PB8_61") (pintype "bidirectional"))
      (node (ref "Y1") (pin "3") (pinfunction "OSC2_3") (pintype "passive"))
    )
    (net (code "53") (name "Net-(U1B-VDDOUT)") (class "Default")
      (node (ref "C10") (pin "1") (pinfunction "1_1") (pintype "passive"))
      (node (ref "C12") (pin "1") (pinfunction "1_1") (pintype "passive"))
      (node (ref "C15") (pin "1") (pinfunction "1_1") (pintype "passive"))
      (node (ref "C8") (pin "1") (pinfunction "1_1") (pintype "passive"))
      (node (ref "L2") (pin "2") (pinfunction "2_2") (pintype "passive"))
      (node (ref "U1") (pin "12") (pinfunction "VDDCORE_12") (pintype "power_in"))
      (node (ref "U1") (pin "24") (pinfunction "VDDCORE_24") (pintype "power_in"))
      (node (ref "U1") (pin "54") (pinfunction "VDDCORE_54") (pintype "power_in"))
      (node (ref "U1") (pin "8") (pinfunction "VDDOUT_8") (pintype "power_in"))
    )
    (net (code "54") (name "Net-(U1B-VDDPLL)") (class "Default")
      (node (ref "C17") (pin "2") (pinfunction "2_2") (pintype "passive"))
      (node (ref "C18") (pin "2") (pinfunction "2_2") (pintype "passive"))
      (node (ref "L2") (pin "1") (pinfunction "1_1") (pintype "passive"))
      (node (ref "U1") (pin "64") (pinfunction "VDDPLL_64") (pintype "power_in"))
    )
    (net (code "55") (name "Net-(U2-BST)") (class "Default")
      (node (ref "C4") (pin "1") (pinfunction "1_1") (pintype "passive"))
      (node (ref "U2") (pin "1") (pinfunction "BST_1") (pintype "passive"))
    )
    (net (code "56") (name "Net-(U2-PGOOD)") (class "Default")
      (node (ref "R3") (pin "1") (pinfunction "1_1") (pintype "passive"))
      (node (ref "U2") (pin "4") (pinfunction "PGOOD_4") (pintype "output"))
    )
    (net (code "57") (name "Net-(U3-VCC)") (class "Default")
      (node (ref "C13") (pin "2") (pinfunction "2_2") (pintype "passive"))
      (node (ref "R6") (pin "2") (pinfunction "2_2") (pintype "passive"))
      (node (ref "U3") (pin "1") (pinfunction "VCC_1") (pintype "passive"))
    )
    (net (code "58") (name "Net-(U4-OUT)") (class "Default")
      (node (ref "C20") (pin "2") (pinfunction "2_2") (pintype "passive"))
      (node (ref "R18") (pin "1") (pinfunction "1_1") (pintype "passive"))
      (node (ref "U4") (pin "5") (pinfunction "OUT_5") (pintype "power_in"))
    )
    (net (code "59") (name "Net-(U6-VCP)") (class "Default")
      (node (ref "C24") (pin "2") (pinfunction "2_2") (pintype "passive"))
      (node (ref "U6") (pin "11") (pinfunction "VCP_11") (pintype "passive"))
    )
    (net (code "60") (name "Net-(U6-VINT)") (class "Default")
      (node (ref "C25") (pin "1") (pinfunction "1_1") (pintype "passive"))
      (node (ref "U6") (pin "14") (pinfunction "VINT_14") (pintype "passive"))
    )
    (net (code "61") (name "Net-(U6-VM)") (class "Default")
      (node (ref "C23") (pin "1") (pinfunction "1_1") (pintype "passive"))
      (node (ref "C24") (pin "1") (pinfunction "1_1") (pintype "passive"))
      (node (ref "R16") (pin "1") (pinfunction "1_1") (pintype "passive"))
      (node (ref "R17") (pin "1") (pinfunction "1_1") (pintype "passive"))
      (node (ref "U6") (pin "12") (pinfunction "VM_12") (pintype "passive"))
    )
    (net (code "62") (name "USB_DETECT") (class "Default")
      (node (ref "R7") (pin "1") (pinfunction "1_1") (pintype "passive"))
      (node (ref "R8") (pin "2") (pinfunction "2_2") (pintype "passive"))
      (node (ref "U1") (pin "35") (pinfunction "PA5/PGMRDY_35") (pintype "bidirectional"))
      (node (ref "USB_DETECT_TP") (pin "1") (pinfunction "1_1") (pintype "passive"))
    )
    (net (code "63") (name "VBUS") (class "Default")
      (node (ref "D2") (pin "1") (pinfunction "A_1") (pintype "passive"))
      (node (ref "H3") (pin "1") (pinfunction "VBUS_1") (pintype "power_in"))
      (node (ref "R7") (pin "2") (pinfunction "2_2") (pintype "passive"))
      (node (ref "VBUS_TP") (pin "1") (pinfunction "1_1") (pintype "passive"))
    )
    (net (code "64") (name "V_BAT") (class "Default")
      (node (ref "C3") (pin "2") (pinfunction "2_2") (pintype "passive"))
      (node (ref "Q1") (pin "2") (pinfunction "2_2") (pintype "passive"))
      (node (ref "R14") (pin "2") (pinfunction "2_2") (pintype "passive"))
      (node (ref "R16") (pin "2") (pinfunction "2_2") (pintype "passive"))
      (node (ref "R17") (pin "2") (pinfunction "2_2") (pintype "passive"))
      (node (ref "R3") (pin "2") (pinfunction "2_2") (pintype "passive"))
      (node (ref "U2") (pin "2") (pinfunction "VIN_2") (pintype "input"))
      (node (ref "U2") (pin "3") (pinfunction "EN_3") (pintype "output"))
      (node (ref "V_BATT_TP") (pin "1") (pinfunction "1_1") (pintype "passive"))
    )
    (net (code "65") (name "nRST") (class "Default")
      (node (ref "H2") (pin "1") (pinfunction "1_1") (pintype "passive"))
      (node (ref "S1") (pin "1") (pintype "passive"))
      (node (ref "U1") (pin "39") (pinfunction "NRST_39") (pintype "bidirectional"))
      (node (ref "nRST_TP") (pin "1") (pinfunction "1_1") (pintype "passive"))
    )
    (net (code "66") (name "unconnected-(H2-Pad3)") (class "Default")
      (node (ref "H2") (pin "3") (pinfunction "3_3") (pintype "passive+no_connect"))
    )
    (net (code "67") (name "unconnected-(H2-Pad9)") (class "Default")
      (node (ref "H2") (pin "9") (pinfunction "9_9") (pintype "passive+no_connect"))
    )
    (net (code "68") (name "unconnected-(H2-Pad10)") (class "Default")
      (node (ref "H2") (pin "10") (pinfunction "10_10") (pintype "passive+no_connect"))
    )
    (net (code "69") (name "unconnected-(H3-ID-Pad4)") (class "Default")
      (node (ref "H3") (pin "4") (pinfunction "ID_4") (pintype "power_in"))
    )
    (net (code "70") (name "unconnected-(H13-Pad8)") (class "Default")
      (node (ref "H13") (pin "8") (pinfunction "8_8") (pintype "passive+no_connect"))
    )
    (net (code "71") (name "unconnected-(U1A-JTAGSEL-Pad50)") (class "Default")
      (node (ref "U1") (pin "50") (pinfunction "JTAGSEL_50") (pintype "input+no_connect"))
    )
    (net (code "72") (name "unconnected-(U1A-PA6{slash}PGMNOE-Pad34)") (class "Default")
      (node (ref "U1") (pin "34") (pinfunction "PA6/PGMNOE_34") (pintype "bidirectional+no_connect"))
    )
    (net (code "73") (name "unconnected-(U1A-PA9{slash}PGMM1-Pad30)") (class "Default")
      (node (ref "U1") (pin "30") (pinfunction "PA9/PGMM1_30") (pintype "bidirectional+no_connect"))
    )
    (net (code "74") (name "unconnected-(U1A-PA10{slash}PGMM2-Pad29)") (class "Default")
      (node (ref "U1") (pin "29") (pinfunction "PA10/PGMM2_29") (pintype "bidirectional+no_connect"))
    )
    (net (code "75") (name "unconnected-(U1A-PA18{slash}PGMD6{slash}AD1-Pad10)") (class "Default")
      (node (ref "U1") (pin "10") (pinfunction "PA18/PGMD6/AD1_10") (pintype "bidirectional+no_connect"))
    )
    (net (code "76") (name "unconnected-(U1A-PA21{slash}PGMD9{slash}AD8-Pad11)") (class "Default")
      (node (ref "U1") (pin "11") (pinfunction "PA21/PGMD9/AD8_11") (pintype "bidirectional+no_connect"))
    )
    (net (code "77") (name "unconnected-(U1A-PA22{slash}PGMD10{slash}AD9-Pad14)") (class "Default")
      (node (ref "U1") (pin "14") (pinfunction "PA22/PGMD10/AD9_14") (pintype "bidirectional+no_connect"))
    )
    (net (code "78") (name "unconnected-(U1A-PA25{slash}PGMD13-Pad25)") (class "Default")
      (node (ref "U1") (pin "25") (pinfunction "PA25/PGMD13_25") (pintype "bidirectional+no_connect"))
    )
    (net (code "79") (name "unconnected-(U1A-PA26{slash}PGMD14-Pad26)") (class "Default")
      (node (ref "U1") (pin "26") (pinfunction "PA26/PGMD14_26") (pintype "bidirectional+no_connect"))
    )
    (net (code "80") (name "unconnected-(U1A-PB1{slash}AD5-Pad4)") (class "Default")
      (node (ref "U1") (pin "4") (pinfunction "PB1/AD5_4") (pintype "bidirectional+no_connect"))
    )
    (net (code "81") (name "unconnected-(U1A-PB2{slash}AD6-Pad5)") (class "Default")
      (node (ref "U1") (pin "5") (pinfunction "PB2/AD6_5") (pintype "bidirectional+no_connect"))
    )
    (net (code "82") (name "unconnected-(U1A-PB3{slash}AD7-Pad6)") (class "Default")
      (node (ref "U1") (pin "6") (pinfunction "PB3/AD7_6") (pintype "bidirectional+no_connect"))
    )
    (net (code "83") (name "unconnected-(U1A-TDI{slash}PB4-Pad33)") (class "Default")
      (node (ref "U1") (pin "33") (pinfunction "TDI/PB4_33") (pintype "bidirectional+no_connect"))
    )
    (net (code "84") (name "unconnected-(U1A-TDO{slash}TRACESWO{slash}PB5-Pad49)") (class "Default")
      (node (ref "U1") (pin "49") (pinfunction "TDO/TRACESWO/PB5_49") (pintype "bidirectional+no_connect"))
    )
    (net (code "85") (name "unconnected-(U1A-TST-Pad40)") (class "Default")
      (node (ref "U1") (pin "40") (pinfunction "TST_40") (pintype "input+no_connect"))
    )
    (net (code "86") (name "unconnected-(U2-NC-Pad6)") (class "Default")
      (node (ref "U2") (pin "6") (pinfunction "NC_6") (pintype "passive+no_connect"))
    )
    (net (code "87") (name "unconnected-(U4-BYP-Pad4)") (class "Default")
      (node (ref "U4") (pin "4") (pinfunction "BYP_4") (pintype "passive"))
    )
    (net (code "88") (name "unconnected-(U5-BYP-Pad4)") (class "Default")
      (node (ref "U5") (pin "4") (pinfunction "BYP_4") (pintype "passive"))
    )
  )
)
